# SH1_-_POWER.net
KiCad netlist of a schematic drawn in Altium Designer
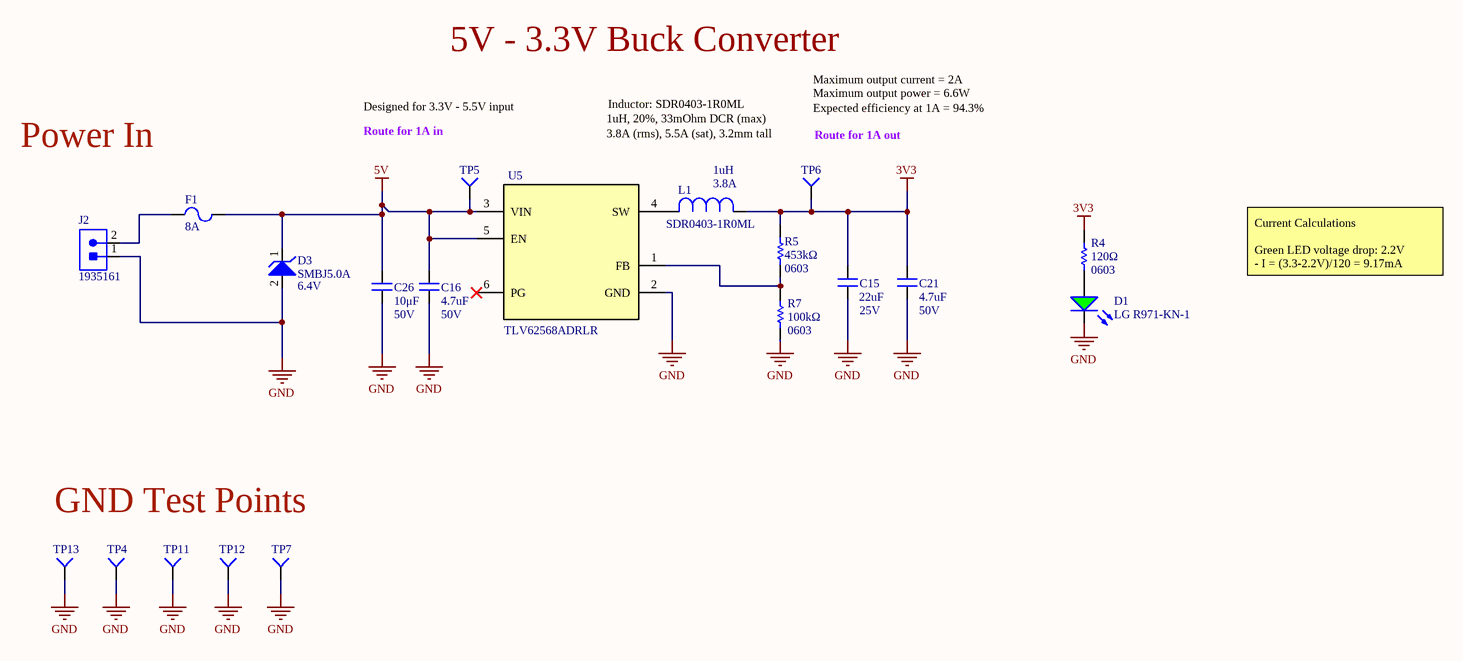
[diagram p0: SH1 - POWER.SchDoc]

(export (version "E")
  (design (tool "Eeschema 10.0.6"))
  (components
    (comp (ref "C15")
      (value "CAP_22uF_25V_1210")
      (footprint "CAPC3225X270N")
      (description "CAP CER 22UF 25V X7R 1210")
      (fields (field (name "VOLTAGE") "25V") (field (name "CAPACITANCE") "22uF"))
      (libsource (lib "UWRT_Schematic_Library_2020") (part "CAP_22uF_25V_1210"))
    )
    (comp (ref "C16")
      (value "CAP_4.7uF_50V_1206")
      (footprint "CAP1206")
      (description "CAP CER 4.7UF 50V X7R 1206")
      (fields (field (name "CAPACITANCE") "4.7uF") (field (name "VOLTAGE") "50V"))
      (libsource (lib "UWRT_Schematic_Library_2020") (part "CAP_4.7uF_50V_1206"))
    )
    (comp (ref "C21")
      (value "CAP_4.7uF_50V_1206")
      (footprint "CAP1206")
      (description "CAP CER 4.7UF 50V X7R 1206")
      (fields (field (name "CAPACITANCE") "4.7uF") (field (name "VOLTAGE") "50V"))
      (libsource (lib "UWRT_Schematic_Library_2020") (part "CAP_4.7uF_50V_1206"))
    )
    (comp (ref "C26")
      (value "10μF")
      (footprint "CAP1206")
      (description "CAP CER 10UF 50V X5R 1206")
      (fields (field (name "VOLTAGE RATING") "50V") (field (name "Comment") "CAP_10uF_50V_1206"))
      (libsource (lib "UWRT_Schematic_Library_2020") (part "CAP_10uF_50V_1206"))
    )
    (comp (ref "D1")
      (value "DIO_LED_G")
      (footprint "LED_0805_GREEN")
      (description "LED GREEN DIFFUSED 0805 SMD")
      (fields (field (name "MANUFACTURER PART NUMBER 1") "LG R971-KN-1"))
      (libsource (lib "UWRT_Schematic_Library_2020") (part "DIO_LED_G"))
    )
    (comp (ref "D3")
      (value "TVS_DIODE_UNIDIR_5V")
      (footprint "SMBJ5.0A")
      (description "TVS DIODE 5V 9.2V DO214AA")
      (fields
        (field (name "REVERSE BREAKDOWN VOLTAGE") "6.4V")
        (field (name "MANUFACTURER PART NUMBER 1") "SMBJ5.0A")
      )
      (libsource (lib "UWRT_Schematic_Library_2020") (part "TVS_DIODE_UNIDIR_5V"))
    )
    (comp (ref "F1")
      (value "FUSE_8A_1206")
      (footprint "FUSE_1206")
      (description "FUSE SMD 8A 24V")
      (fields (field (name "CURRENT RATING") "8A") (field (name "LCSC PART #") "C311032"))
      (libsource (lib "UWRT_Schematic_Library_2020") (part "FUSE_8A_1206"))
    )
    (comp (ref "J2")
      (value "CON_2M_TERM")
      (footprint "1935161")
      (description "TERM BLK 2POS SIDE ENTRY 5MM")
      (fields (field (name "VOLTAGE") "300V") (field (name "MANUFACTURER PART NUMBER 1") "1935161"))
      (libsource (lib "UWRT_Schematic_Library_2020") (part "CON_2M_TERM"))
    )
    (comp (ref "L1")
      (value "1uH")
      (footprint "IND_BOURNS_SDR04")
      (description "FIXED IND 1UH 3.8A 33 MOHM SMD")
      (fields
        (field (name "MANUFACTURER PART NUMBER 1") "SDR0403-1R0ML")
        (field (name "TOLERANCE") "±20%")
        (field (name "CURRENT RATING") "3.8A")
        (field (name "Comment") "IND_1uH_3.8A")
      )
      (libsource (lib "UWRT_Schematic_Library_2020") (part "IND_1uH_3.8A"))
    )
    (comp (ref "R4")
      (value "120Ω")
      (footprint "RESC0603")
      (description "RES 120 OHM 5% 1/10W 0603")
      (fields (field (name "PACKAGE/FOOTPRINT") "0603") (field (name "Comment") "RES_120Ω_0603"))
      (libsource (lib "UWRT_Schematic_Library_2020") (part "RES_120Ω_0603_5%"))
    )
    (comp (ref "R5")
      (value "453kΩ")
      (footprint "RESC0603")
      (description "RES 453K OHM 1% 1/10W 0603")
      (fields
        (field (name "TOLERANCE") "1%")
        (field (name "PACKAGE/FOOTPRINT") "0603")
        (field (name "Comment") "RES_453kΩ_0603_1%")
      )
      (libsource (lib "UWRT_Schematic_Library_2020") (part "RES_453kΩ_0603_1%"))
    )
    (comp (ref "R7")
      (value "100kΩ")
      (footprint "RESC0603(1608)_N")
      (description "RES 100K OHM 1% 1/10W 0603")
      (fields
        (field (name "TOLERANCE") "1%")
        (field (name "PACKAGE/FOOTPRINT") "0603")
        (field (name "Comment") "RES_100kΩ_0603_1%")
      )
      (libsource (lib "UWRT_Schematic_Library_2020") (part "RES_100kΩ_0603_1%"))
    )
    (comp (ref "TP4")
      (value "TESTPOINT_1MM_SQUARE")
      (footprint "TESTPOINT_SQUARE_1MM")
      (description "TESTPOINT 1MM SQUARE")
      (libsource (lib "UWRT_Schematic_Library_2020") (part "TESTPOINT_1MM_SQUARE"))
    )
    (comp (ref "TP5")
      (value "TESTPOINT_SMD_LOOP")
      (footprint "S1751-46R")
      (description "PC TEST POINT SMD")
      (libsource (lib "UWRT_Schematic_Library_2020") (part "TESTPOINT_SMD_LOOP"))
    )
    (comp (ref "TP6")
      (value "TESTPOINT_SMD_LOOP")
      (footprint "S1751-46R")
      (description "PC TEST POINT SMD")
      (libsource (lib "UWRT_Schematic_Library_2020") (part "TESTPOINT_SMD_LOOP"))
    )
    (comp (ref "TP7")
      (value "TESTPOINT_1MM_SQUARE")
      (footprint "TESTPOINT_SQUARE_1MM")
      (description "TESTPOINT 1MM SQUARE")
      (libsource (lib "UWRT_Schematic_Library_2020") (part "TESTPOINT_1MM_SQUARE"))
    )
    (comp (ref "TP11")
      (value "TESTPOINT_1MM_SQUARE")
      (footprint "TESTPOINT_SQUARE_1MM")
      (description "TESTPOINT 1MM SQUARE")
      (libsource (lib "UWRT_Schematic_Library_2020") (part "TESTPOINT_1MM_SQUARE"))
    )
    (comp (ref "TP12")
      (value "TESTPOINT_1MM_SQUARE")
      (footprint "TESTPOINT_SQUARE_1MM")
      (description "TESTPOINT 1MM SQUARE")
      (libsource (lib "UWRT_Schematic_Library_2020") (part "TESTPOINT_1MM_SQUARE"))
    )
    (comp (ref "TP13")
      (value "TESTPOINT_SMD_LOOP")
      (footprint "S1751-46R")
      (description "PC TEST POINT SMD")
      (libsource (lib "UWRT_Schematic_Library_2020") (part "TESTPOINT_SMD_LOOP"))
    )
    (comp (ref "U5")
      (value "TLV62568ADRLR")
      (footprint "SOT50P160X60-6N")
      (description "IC REG BUCK ADJUSTABLE 2A SOT563")
      (libsource (lib "UWRT_Schematic_Library_2020") (part "TLV62568ADRLR"))
    )
  )
  (nets
    (net (code "1") (name "3V3") (class "Default")
      (node (ref "C15") (pin "2") (pinfunction "2_2") (pintype "passive"))
      (node (ref "C21") (pin "2") (pinfunction "2_2") (pintype "passive"))
      (node (ref "L1") (pin "2") (pinfunction "2_2") (pintype "passive"))
      (node (ref "R4") (pin "2") (pinfunction "2_2") (pintype "passive"))
      (node (ref "R5") (pin "2") (pinfunction "2_2") (pintype "passive"))
      (node (ref "TP6") (pin "1") (pinfunction "=value_1") (pintype "passive"))
    )
    (net (code "2") (name "5V") (class "Default")
      (node (ref "C16") (pin "2") (pinfunction "2_2") (pintype "passive"))
      (node (ref "C26") (pin "2") (pinfunction "2_2") (pintype "passive"))
      (node (ref "D3") (pin "1") (pinfunction "1_1") (pintype "passive"))
      (node (ref "F1") (pin "2") (pinfunction "2_2") (pintype "passive"))
      (node (ref "TP5") (pin "1") (pinfunction "=value_1") (pintype "passive"))
      (node (ref "U5") (pin "3") (pinfunction "VIN_3") (pintype "power_in"))
      (node (ref "U5") (pin "5") (pinfunction "EN_5") (pintype "passive"))
    )
    (net (code "3") (name "GND") (class "Default")
      (node (ref "C15") (pin "1") (pinfunction "1_1") (pintype "passive"))
      (node (ref "C16") (pin "1") (pinfunction "1_1") (pintype "passive"))
      (node (ref "C21") (pin "1") (pinfunction "1_1") (pintype "passive"))
      (node (ref "C26") (pin "1") (pinfunction "1_1") (pintype "passive"))
      (node (ref "D1") (pin "2") (pinfunction "K_2") (pintype "passive"))
      (node (ref "D3") (pin "2") (pinfunction "2_2") (pintype "passive"))
      (node (ref "J2") (pin "1") (pinfunction "1_1") (pintype "passive"))
      (node (ref "R7") (pin "1") (pinfunction "1_1") (pintype "passive"))
      (node (ref "TP11") (pin "1") (pinfunction "=value_1") (pintype "passive"))
      (node (ref "TP12") (pin "1") (pinfunction "=value_1") (pintype "passive"))
      (node (ref "TP13") (pin "1") (pinfunction "=value_1") (pintype "passive"))
      (node (ref "TP4") (pin "1") (pinfunction "=value_1") (pintype "passive"))
      (node (ref "TP7") (pin "1") (pinfunction "=value_1") (pintype "passive"))
      (node (ref "U5") (pin "2") (pinfunction "GND_2") (pintype "power_in"))
    )
    (net (code "4") (name "Net-(D1-A)") (class "Default")
      (node (ref "D1") (pin "1") (pinfunction "A_1") (pintype "passive"))
      (node (ref "R4") (pin "1") (pinfunction "1_1") (pintype "passive"))
    )
    (net (code "5") (name "Net-(F1-Pad1)") (class "Default")
      (node (ref "F1") (pin "1") (pinfunction "1_1") (pintype "passive"))
      (node (ref "J2") (pin "2") (pinfunction "2_2") (pintype "passive"))
    )
    (net (code "6") (name "Net-(U5-FB)") (class "Default")
      (node (ref "R5") (pin "1") (pinfunction "1_1") (pintype "passive"))
      (node (ref "R7") (pin "2") (pinfunction "2_2") (pintype "passive"))
      (node (ref "U5") (pin "1") (pinfunction "FB_1") (pintype "passive"))
    )
    (net (code "7") (name "Net-(U5-SW)") (class "Default")
      (node (ref "L1") (pin "1") (pinfunction "1_1") (pintype "passive"))
      (node (ref "U5") (pin "4") (pinfunction "SW_4") (pintype "power_in"))
    )
    (net (code "8") (name "unconnected-(U5-PG-Pad6)") (class "Default")
      (node (ref "U5") (pin "6") (pinfunction "PG_6") (pintype "open_collector+no_connect"))
    )
  )
)
